# week7.net
KiCad netlist of a schematic drawn in EAGLE
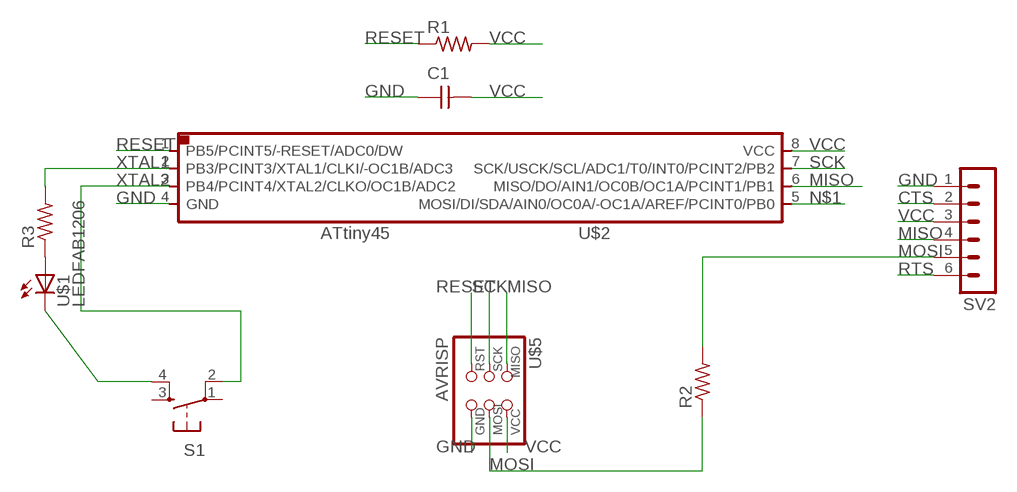
[diagram p0: schematic, sheet 1]

(export (version "E")
  (design (tool "Eeschema 10.0.6"))
  (components
    (comp (ref "C1")
      (value "CAP-UNPOLARIZED")
      (footprint "eagle-import:C1206")
      (libsource (lib "eagle-import") (part "CAP-UNPOLARIZED"))
    )
    (comp (ref "R1")
      (value "RES-US1206FAB")
      (footprint "eagle-import:R1206FAB")
      (libsource (lib "eagle-import") (part "RES-US1206FAB"))
    )
    (comp (ref "R2")
      (value "RES-US1206FAB")
      (footprint "eagle-import:R1206FAB")
      (libsource (lib "eagle-import") (part "RES-US1206FAB"))
    )
    (comp (ref "R3")
      (value "RES-US1206FAB")
      (footprint "eagle-import:R1206FAB")
      (libsource (lib "eagle-import") (part "RES-US1206FAB"))
    )
    (comp (ref "S1")
      (value "6MM_SWITCH6MM_SWITCH")
      (footprint "eagle-import:6MM_SWITCH")
      (libsource (lib "eagle-import") (part "6MM_SWITCH6MM_SWITCH"))
    )
    (comp (ref "SV2")
      (value "MA06-1")
      (footprint "eagle-import:MA06-1")
      (libsource (lib "eagle-import") (part "MA06-1"))
    )
    (comp (ref "U$1")
      (value "LEDFAB1206")
      (footprint "eagle-import:LED1206FAB")
      (libsource (lib "eagle-import") (part "LEDFAB1206"))
    )
    (comp (ref "U$2")
      (value "ATTINY45SI")
      (footprint "eagle-import:SOIC8")
      (libsource (lib "eagle-import") (part "ATTINY45SI"))
    )
    (comp (ref "U$5")
      (value "AVRISP")
      (footprint "eagle-import:2X03")
      (libsource (lib "eagle-import") (part "AVRISP"))
    )
  )
  (nets
    (net (code "1") (name "/CTS") (class "Default")
      (node (ref "SV2") (pin "2") (pinfunction "2_2") (pintype "passive"))
    )
    (net (code "2") (name "/GND") (class "Default")
      (node (ref "C1") (pin "1") (pinfunction "1_1") (pintype "passive"))
      (node (ref "S1") (pin "4") (pinfunction "S1_4") (pintype "passive"))
      (node (ref "SV2") (pin "1") (pinfunction "1_1") (pintype "passive"))
      (node (ref "U$1") (pin "2") (pinfunction "C_2") (pintype "passive"))
      (node (ref "U$2") (pin "4") (pinfunction "GND_4") (pintype "bidirectional"))
      (node (ref "U$5") (pin "6") (pinfunction "GND_6") (pintype "passive"))
    )
    (net (code "3") (name "/MISO") (class "Default")
      (node (ref "SV2") (pin "4") (pinfunction "4_4") (pintype "passive"))
      (node (ref "U$2") (pin "6") (pinfunction "MISO/DO/AIN1/OC0B/OC1A/PCINT1/PB1_6") (pintype "bidirectional"))
      (node (ref "U$5") (pin "1") (pinfunction "MISO_1") (pintype "passive"))
    )
    (net (code "4") (name "/MOSI") (class "Default")
      (node (ref "R2") (pin "1") (pinfunction "1_1") (pintype "passive"))
      (node (ref "R2") (pin "2") (pinfunction "2_2") (pintype "passive"))
      (node (ref "SV2") (pin "5") (pinfunction "5_5") (pintype "passive"))
      (node (ref "U$5") (pin "4") (pinfunction "MOSI_4") (pintype "passive"))
    )
    (net (code "5") (name "/N$1") (class "Default")
      (node (ref "U$2") (pin "5") (pinfunction "MOSI/DI/SDA/AIN0/OC0A/-OC1A/AREF/PCINT0/PB0_5") (pintype "bidirectional"))
    )
    (net (code "6") (name "/RESET") (class "Default")
      (node (ref "R1") (pin "1") (pinfunction "1_1") (pintype "passive"))
      (node (ref "U$2") (pin "1") (pinfunction "PB5/PCINT5/-RESET/ADC0/DW_1") (pintype "bidirectional"))
      (node (ref "U$5") (pin "5") (pinfunction "RST_5") (pintype "passive"))
    )
    (net (code "7") (name "/RTS") (class "Default")
      (node (ref "SV2") (pin "6") (pinfunction "6_6") (pintype "passive"))
    )
    (net (code "8") (name "/SCK") (class "Default")
      (node (ref "U$2") (pin "7") (pinfunction "SCK/USCK/SCL/ADC1/T0/INT0/PCINT2/PB2_7") (pintype "bidirectional"))
      (node (ref "U$5") (pin "3") (pinfunction "SCK_3") (pintype "passive"))
    )
    (net (code "9") (name "/VCC") (class "Default")
      (node (ref "C1") (pin "2") (pinfunction "2_2") (pintype "passive"))
      (node (ref "R1") (pin "2") (pinfunction "2_2") (pintype "passive"))
      (node (ref "SV2") (pin "3") (pinfunction "3_3") (pintype "passive"))
      (node (ref "U$2") (pin "8") (pinfunction "VCC_8") (pintype "bidirectional"))
      (node (ref "U$5") (pin "2") (pinfunction "VCC_2") (pintype "passive"))
    )
    (net (code "10") (name "/XTAL1") (class "Default")
      (node (ref "R3") (pin "2") (pinfunction "2_2") (pintype "passive"))
      (node (ref "U$2") (pin "2") (pinfunction "PB3/PCINT3/XTAL1/CLKI/-OC1B/ADC3_2") (pintype "bidirectional"))
    )
    (net (code "11") (name "/XTAL2") (class "Default")
      (node (ref "S1") (pin "2") (pinfunction "P1_2") (pintype "passive"))
      (node (ref "U$2") (pin "3") (pinfunction "PB4/PCINT4/XTAL2/CLKO/OC1B/ADC2_3") (pintype "bidirectional"))
    )
    (net (code "12") (name "Net-(U$1-A)") (class "Default")
      (node (ref "R3") (pin "1") (pinfunction "1_1") (pintype "passive"))
      (node (ref "U$1") (pin "1") (pinfunction "A_1") (pintype "passive"))
    )
    (net (code "13") (name "unconnected-(S1-P-Pad1)") (class "Default")
      (node (ref "S1") (pin "1") (pinfunction "P_1") (pintype "passive"))
    )
    (net (code "14") (name "unconnected-(S1-S-Pad3)") (class "Default")
      (node (ref "S1") (pin "3") (pinfunction "S_3") (pintype "passive"))
    )
  )
)
